# Hermit_Board_Rev_A4.net
KiCad netlist of a schematic drawn in EAGLE
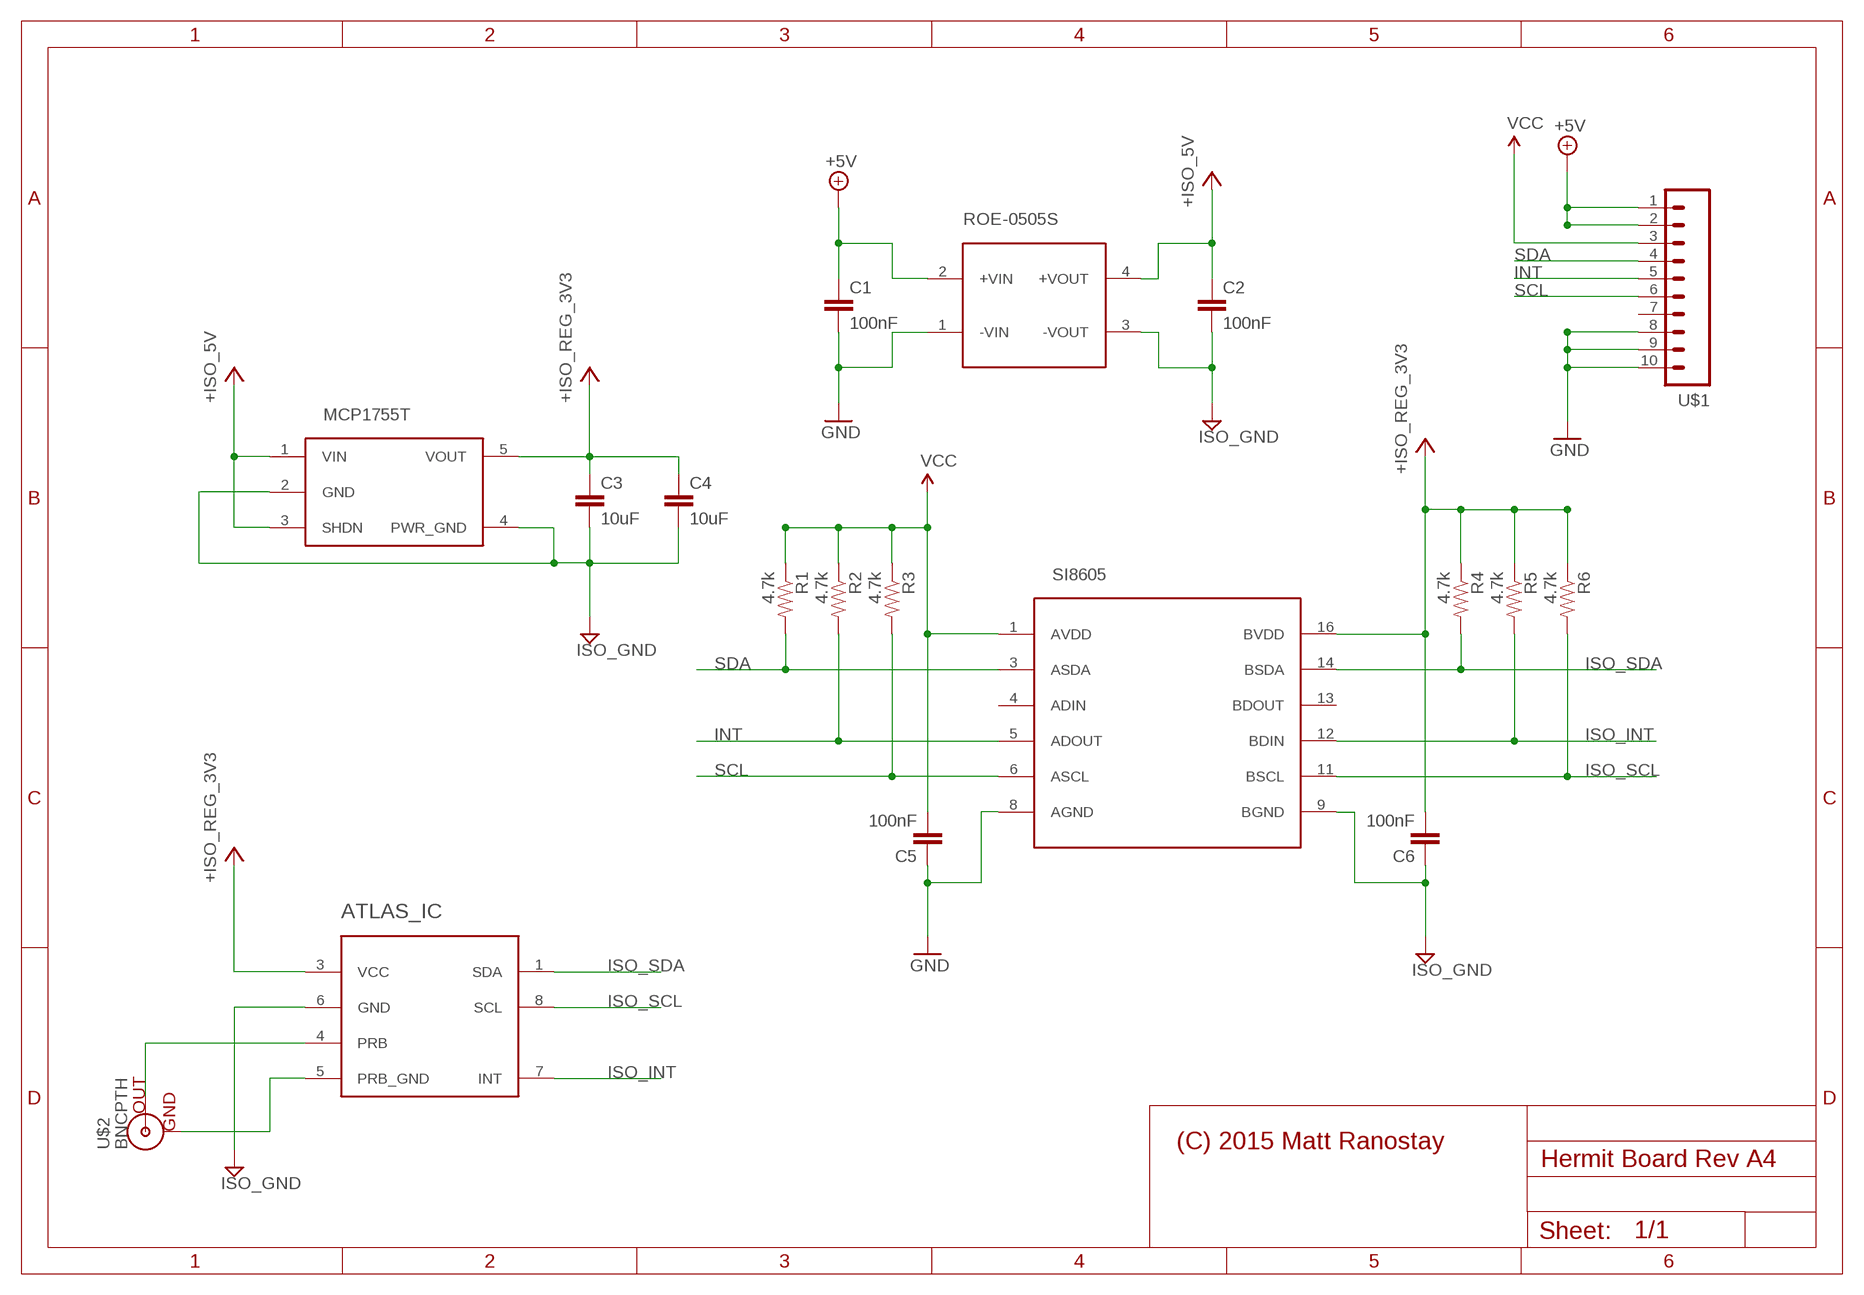
[diagram p0: schematic, sheet 1]

(export (version "E")
  (design (tool "Eeschema 10.0.6"))
  (components
    (comp (ref "ATLAS_IC")
      (value "ATLAS-OEM")
      (footprint "eagle-import:ATLAS-OEM")
      (libsource (lib "eagle-import") (part "ATLAS-OEM"))
    )
    (comp (ref "C1")
      (value "100nF")
      (footprint "eagle-import:0805")
      (libsource (lib "eagle-import") (part "CAP0805"))
    )
    (comp (ref "C2")
      (value "100nF")
      (footprint "eagle-import:0805")
      (libsource (lib "eagle-import") (part "CAP0805"))
    )
    (comp (ref "C3")
      (value "10uF")
      (footprint "eagle-import:0805")
      (libsource (lib "eagle-import") (part "CAP0805"))
    )
    (comp (ref "C4")
      (value "10uF")
      (footprint "eagle-import:0805")
      (libsource (lib "eagle-import") (part "CAP0805"))
    )
    (comp (ref "C5")
      (value "100nF")
      (footprint "eagle-import:0805")
      (libsource (lib "eagle-import") (part "CAP0805"))
    )
    (comp (ref "C6")
      (value "100nF")
      (footprint "eagle-import:0805")
      (libsource (lib "eagle-import") (part "CAP0805"))
    )
    (comp (ref "MCP1755T")
      (value "MCP1755T")
      (footprint "eagle-import:SOT-23-5")
      (libsource (lib "eagle-import") (part "MCP1755T"))
    )
    (comp (ref "R1")
      (value "4.7k")
      (footprint "eagle-import:0805")
      (libsource (lib "eagle-import") (part "RESISTOR0805-RES"))
    )
    (comp (ref "R2")
      (value "4.7k")
      (footprint "eagle-import:0805")
      (libsource (lib "eagle-import") (part "RESISTOR0805-RES"))
    )
    (comp (ref "R3")
      (value "4.7k")
      (footprint "eagle-import:0805")
      (libsource (lib "eagle-import") (part "RESISTOR0805-RES"))
    )
    (comp (ref "R4")
      (value "4.7k")
      (footprint "eagle-import:0805")
      (libsource (lib "eagle-import") (part "RESISTOR0805-RES"))
    )
    (comp (ref "R5")
      (value "4.7k")
      (footprint "eagle-import:0805")
      (libsource (lib "eagle-import") (part "RESISTOR0805-RES"))
    )
    (comp (ref "R6")
      (value "4.7k")
      (footprint "eagle-import:0805")
      (libsource (lib "eagle-import") (part "RESISTOR0805-RES"))
    )
    (comp (ref "ROE-0505S")
      (value "ROE-0505S")
      (footprint "eagle-import:SIP4")
      (libsource (lib "eagle-import") (part "ROE-0505S"))
    )
    (comp (ref "SI8605")
      (value "SI8605")
      (footprint "eagle-import:SOIC16-1.27-10X3.9MM")
      (libsource (lib "eagle-import") (part "SI8605"))
    )
    (comp (ref "U$1")
      (value "M10SILK_FEMALE_PTH")
      (footprint "eagle-import:1X10")
      (libsource (lib "eagle-import") (part "M10SILK_FEMALE_PTH"))
    )
    (comp (ref "U$2")
      (value "BNCPTH")
      (footprint "eagle-import:BNC")
      (libsource (lib "eagle-import") (part "BNCPTH"))
    )
  )
  (nets
    (net (code "1") (name "+5V") (class "Default")
      (node (ref "C1") (pin "1") (pinfunction "1_1") (pintype "passive"))
      (node (ref "ROE-0505S") (pin "2") (pinfunction "+VIN_2") (pintype "power_in"))
      (node (ref "U$1") (pin "1") (pinfunction "1_1") (pintype "passive"))
      (node (ref "U$1") (pin "2") (pinfunction "2_2") (pintype "passive"))
    )
    (net (code "2") (name "+ISO_5V") (class "Default")
      (node (ref "C2") (pin "1") (pinfunction "1_1") (pintype "passive"))
      (node (ref "MCP1755T") (pin "1") (pinfunction "VIN_1") (pintype "power_in"))
      (node (ref "MCP1755T") (pin "3") (pinfunction "SHDN_3") (pintype "input"))
      (node (ref "ROE-0505S") (pin "4") (pinfunction "+VOUT_4") (pintype "power_in"))
    )
    (net (code "3") (name "+ISO_REG_3V3") (class "Default")
      (node (ref "ATLAS_IC") (pin "3") (pinfunction "VCC_3") (pintype "power_in"))
      (node (ref "C3") (pin "1") (pinfunction "1_1") (pintype "passive"))
      (node (ref "C4") (pin "1") (pinfunction "1_1") (pintype "passive"))
      (node (ref "C6") (pin "2") (pinfunction "2_2") (pintype "passive"))
      (node (ref "MCP1755T") (pin "5") (pinfunction "VOUT_5") (pintype "power_in"))
      (node (ref "R4") (pin "1") (pinfunction "1_1") (pintype "passive"))
      (node (ref "R5") (pin "1") (pinfunction "1_1") (pintype "passive"))
      (node (ref "R6") (pin "1") (pinfunction "1_1") (pintype "passive"))
      (node (ref "SI8605") (pin "16") (pinfunction "BVDD_16") (pintype "power_in"))
    )
    (net (code "4") (name "/INT") (class "Default")
      (node (ref "R2") (pin "2") (pinfunction "2_2") (pintype "passive"))
      (node (ref "SI8605") (pin "5") (pinfunction "ADOUT_5") (pintype "output"))
      (node (ref "U$1") (pin "5") (pinfunction "5_5") (pintype "passive"))
    )
    (net (code "5") (name "/ISO_INT") (class "Default")
      (node (ref "ATLAS_IC") (pin "7") (pinfunction "INT_7") (pintype "output"))
      (node (ref "R5") (pin "2") (pinfunction "2_2") (pintype "passive"))
      (node (ref "SI8605") (pin "12") (pinfunction "BDIN_12") (pintype "input"))
    )
    (net (code "6") (name "/ISO_SCL") (class "Default")
      (node (ref "ATLAS_IC") (pin "8") (pinfunction "SCL_8") (pintype "bidirectional"))
      (node (ref "R6") (pin "2") (pinfunction "2_2") (pintype "passive"))
      (node (ref "SI8605") (pin "11") (pinfunction "BSCL_11") (pintype "bidirectional"))
    )
    (net (code "7") (name "/ISO_SDA") (class "Default")
      (node (ref "ATLAS_IC") (pin "1") (pinfunction "SDA_1") (pintype "bidirectional"))
      (node (ref "R4") (pin "2") (pinfunction "2_2") (pintype "passive"))
      (node (ref "SI8605") (pin "14") (pinfunction "BSDA_14") (pintype "bidirectional"))
    )
    (net (code "8") (name "/SCL") (class "Default")
      (node (ref "R3") (pin "2") (pinfunction "2_2") (pintype "passive"))
      (node (ref "SI8605") (pin "6") (pinfunction "ASCL_6") (pintype "bidirectional"))
      (node (ref "U$1") (pin "6") (pinfunction "6_6") (pintype "passive"))
    )
    (net (code "9") (name "/SDA") (class "Default")
      (node (ref "R1") (pin "2") (pinfunction "2_2") (pintype "passive"))
      (node (ref "SI8605") (pin "3") (pinfunction "ASDA_3") (pintype "bidirectional"))
      (node (ref "U$1") (pin "4") (pinfunction "4_4") (pintype "passive"))
    )
    (net (code "10") (name "GND") (class "Default")
      (node (ref "C1") (pin "2") (pinfunction "2_2") (pintype "passive"))
      (node (ref "C5") (pin "1") (pinfunction "1_1") (pintype "passive"))
      (node (ref "ROE-0505S") (pin "1") (pinfunction "-VIN_1") (pintype "power_in"))
      (node (ref "SI8605") (pin "8") (pinfunction "AGND_8") (pintype "power_in"))
      (node (ref "U$1") (pin "10") (pinfunction "10_10") (pintype "passive"))
      (node (ref "U$1") (pin "8") (pinfunction "8_8") (pintype "passive"))
      (node (ref "U$1") (pin "9") (pinfunction "9_9") (pintype "passive"))
    )
    (net (code "11") (name "ISO_GND") (class "Default")
      (node (ref "ATLAS_IC") (pin "6") (pinfunction "GND_6") (pintype "power_in"))
      (node (ref "C2") (pin "2") (pinfunction "2_2") (pintype "passive"))
      (node (ref "C3") (pin "2") (pinfunction "2_2") (pintype "passive"))
      (node (ref "C4") (pin "2") (pinfunction "2_2") (pintype "passive"))
      (node (ref "C6") (pin "1") (pinfunction "1_1") (pintype "passive"))
      (node (ref "MCP1755T") (pin "2") (pinfunction "GND_2") (pintype "power_in"))
      (node (ref "MCP1755T") (pin "4") (pinfunction "PWR_GND_4") (pintype "power_in"))
      (node (ref "ROE-0505S") (pin "3") (pinfunction "-VOUT_3") (pintype "power_in"))
      (node (ref "SI8605") (pin "9") (pinfunction "BGND_9") (pintype "power_in"))
    )
    (net (code "12") (name "Net-(ATLAS_IC-PRB)") (class "Default")
      (node (ref "ATLAS_IC") (pin "4") (pinfunction "PRB_4") (pintype "input"))
      (node (ref "U$2") (pin "S") (pinfunction "OUT_S") (pintype "bidirectional"))
    )
    (net (code "13") (name "Net-(ATLAS_IC-PRB_GND)") (class "Default")
      (node (ref "ATLAS_IC") (pin "5") (pinfunction "PRB_GND_5") (pintype "power_in"))
      (node (ref "U$2") (pin "GND") (pinfunction "GND_GND") (pintype "bidirectional"))
    )
    (net (code "14") (name "VCC") (class "Default")
      (node (ref "C5") (pin "2") (pinfunction "2_2") (pintype "passive"))
      (node (ref "R1") (pin "1") (pinfunction "1_1") (pintype "passive"))
      (node (ref "R2") (pin "1") (pinfunction "1_1") (pintype "passive"))
      (node (ref "R3") (pin "1") (pinfunction "1_1") (pintype "passive"))
      (node (ref "SI8605") (pin "1") (pinfunction "AVDD_1") (pintype "power_in"))
      (node (ref "U$1") (pin "3") (pinfunction "3_3") (pintype "passive"))
    )
    (net (code "15") (name "unconnected-(SI8605-ADIN-Pad4)") (class "Default")
      (node (ref "SI8605") (pin "4") (pinfunction "ADIN_4") (pintype "input"))
    )
    (net (code "16") (name "unconnected-(SI8605-BDOUT-Pad13)") (class "Default")
      (node (ref "SI8605") (pin "13") (pinfunction "BDOUT_13") (pintype "output"))
    )
    (net (code "17") (name "unconnected-(U$1-Pad7)") (class "Default")
      (node (ref "U$1") (pin "7") (pinfunction "7_7") (pintype "passive"))
    )
  )
)
